# LEDS2.net
KiCad netlist of a schematic drawn in Altium Designer
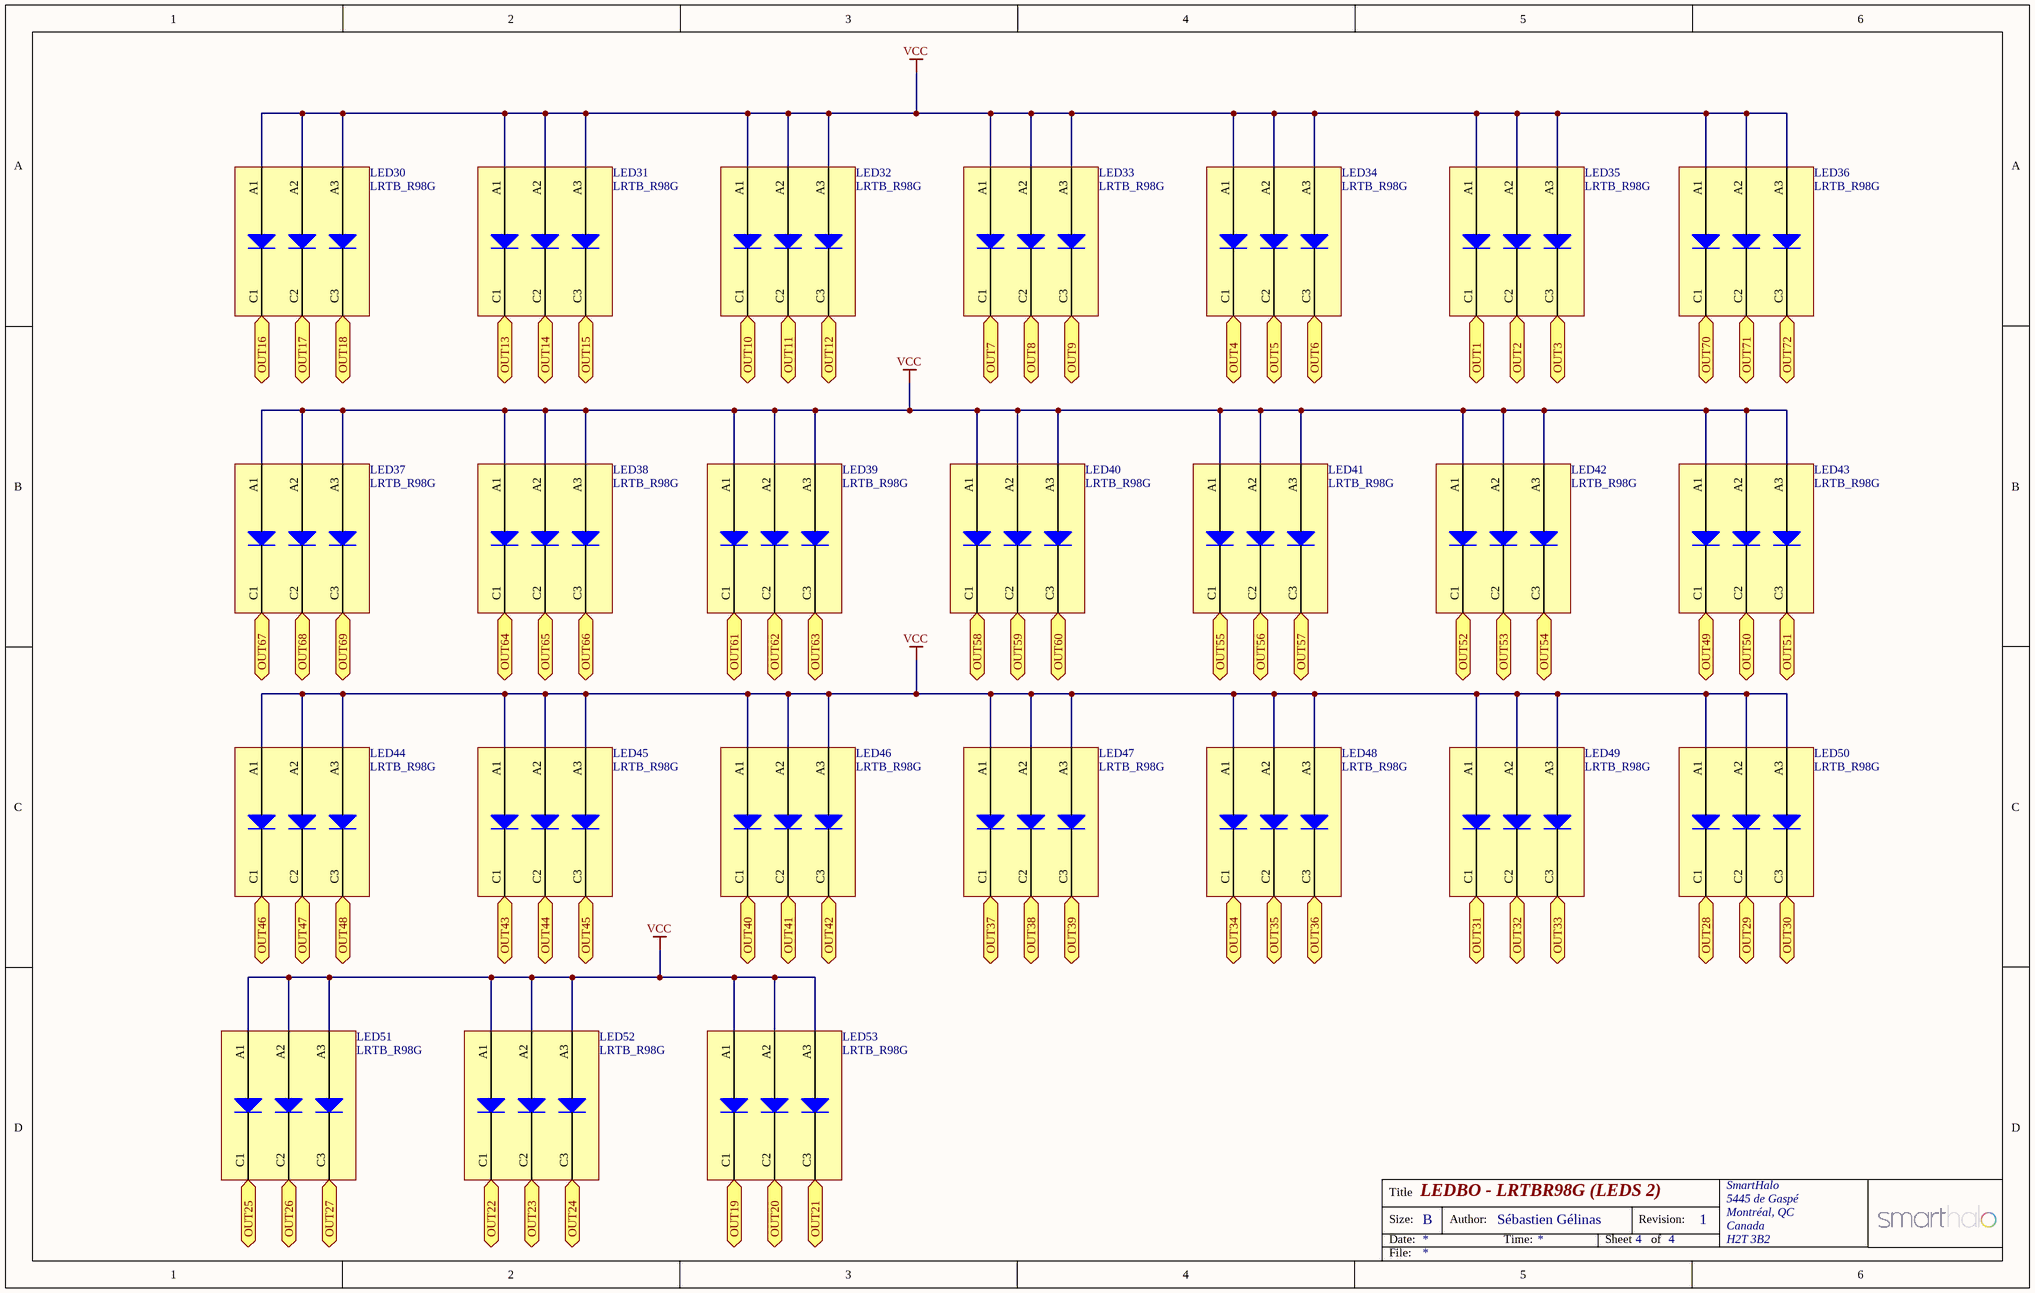
[diagram p0: LEDS2.SchDoc]

(export (version "E")
  (design (tool "Eeschema 10.0.6"))
  (components
    (comp (ref "LED30")
      (value "LRTB_R98G")
      (footprint "LRTB_R98G")
      (description "IC RGB LED OSRAM")
      (fields (field (name "MANUFACTURER") "OSRAM"))
      (libsource (lib "SmartHalo_Symbols") (part "LRTB_R98G"))
    )
    (comp (ref "LED31")
      (value "LRTB_R98G")
      (footprint "LRTB_R98G")
      (description "IC RGB LED OSRAM")
      (fields (field (name "MANUFACTURER") "OSRAM"))
      (libsource (lib "SmartHalo_Symbols") (part "LRTB_R98G"))
    )
    (comp (ref "LED32")
      (value "LRTB_R98G")
      (footprint "LRTB_R98G")
      (description "IC RGB LED OSRAM")
      (fields (field (name "MANUFACTURER") "OSRAM"))
      (libsource (lib "SmartHalo_Symbols") (part "LRTB_R98G"))
    )
    (comp (ref "LED33")
      (value "LRTB_R98G")
      (footprint "LRTB_R98G")
      (description "IC RGB LED OSRAM")
      (fields (field (name "MANUFACTURER") "OSRAM"))
      (libsource (lib "SmartHalo_Symbols") (part "LRTB_R98G"))
    )
    (comp (ref "LED34")
      (value "LRTB_R98G")
      (footprint "LRTB_R98G")
      (description "IC RGB LED OSRAM")
      (fields (field (name "MANUFACTURER") "OSRAM"))
      (libsource (lib "SmartHalo_Symbols") (part "LRTB_R98G"))
    )
    (comp (ref "LED35")
      (value "LRTB_R98G")
      (footprint "LRTB_R98G")
      (description "IC RGB LED OSRAM")
      (fields (field (name "MANUFACTURER") "OSRAM"))
      (libsource (lib "SmartHalo_Symbols") (part "LRTB_R98G"))
    )
    (comp (ref "LED36")
      (value "LRTB_R98G")
      (footprint "LRTB_R98G")
      (description "IC RGB LED OSRAM")
      (fields (field (name "MANUFACTURER") "OSRAM"))
      (libsource (lib "SmartHalo_Symbols") (part "LRTB_R98G"))
    )
    (comp (ref "LED37")
      (value "LRTB_R98G")
      (footprint "LRTB_R98G")
      (description "IC RGB LED OSRAM")
      (fields (field (name "MANUFACTURER") "OSRAM"))
      (libsource (lib "SmartHalo_Symbols") (part "LRTB_R98G"))
    )
    (comp (ref "LED38")
      (value "LRTB_R98G")
      (footprint "LRTB_R98G")
      (description "IC RGB LED OSRAM")
      (fields (field (name "MANUFACTURER") "OSRAM"))
      (libsource (lib "SmartHalo_Symbols") (part "LRTB_R98G"))
    )
    (comp (ref "LED39")
      (value "LRTB_R98G")
      (footprint "LRTB_R98G")
      (description "IC RGB LED OSRAM")
      (fields (field (name "MANUFACTURER") "OSRAM"))
      (libsource (lib "SmartHalo_Symbols") (part "LRTB_R98G"))
    )
    (comp (ref "LED40")
      (value "LRTB_R98G")
      (footprint "LRTB_R98G")
      (description "IC RGB LED OSRAM")
      (fields (field (name "MANUFACTURER") "OSRAM"))
      (libsource (lib "SmartHalo_Symbols") (part "LRTB_R98G"))
    )
    (comp (ref "LED41")
      (value "LRTB_R98G")
      (footprint "LRTB_R98G")
      (description "IC RGB LED OSRAM")
      (fields (field (name "MANUFACTURER") "OSRAM"))
      (libsource (lib "SmartHalo_Symbols") (part "LRTB_R98G"))
    )
    (comp (ref "LED42")
      (value "LRTB_R98G")
      (footprint "LRTB_R98G")
      (description "IC RGB LED OSRAM")
      (fields (field (name "MANUFACTURER") "OSRAM"))
      (libsource (lib "SmartHalo_Symbols") (part "LRTB_R98G"))
    )
    (comp (ref "LED43")
      (value "LRTB_R98G")
      (footprint "LRTB_R98G")
      (description "IC RGB LED OSRAM")
      (fields (field (name "MANUFACTURER") "OSRAM"))
      (libsource (lib "SmartHalo_Symbols") (part "LRTB_R98G"))
    )
    (comp (ref "LED44")
      (value "LRTB_R98G")
      (footprint "LRTB_R98G")
      (description "IC RGB LED OSRAM")
      (fields (field (name "MANUFACTURER") "OSRAM"))
      (libsource (lib "SmartHalo_Symbols") (part "LRTB_R98G"))
    )
    (comp (ref "LED45")
      (value "LRTB_R98G")
      (footprint "LRTB_R98G")
      (description "IC RGB LED OSRAM")
      (fields (field (name "MANUFACTURER") "OSRAM"))
      (libsource (lib "SmartHalo_Symbols") (part "LRTB_R98G"))
    )
    (comp (ref "LED46")
      (value "LRTB_R98G")
      (footprint "LRTB_R98G")
      (description "IC RGB LED OSRAM")
      (fields (field (name "MANUFACTURER") "OSRAM"))
      (libsource (lib "SmartHalo_Symbols") (part "LRTB_R98G"))
    )
    (comp (ref "LED47")
      (value "LRTB_R98G")
      (footprint "LRTB_R98G")
      (description "IC RGB LED OSRAM")
      (fields (field (name "MANUFACTURER") "OSRAM"))
      (libsource (lib "SmartHalo_Symbols") (part "LRTB_R98G"))
    )
    (comp (ref "LED48")
      (value "LRTB_R98G")
      (footprint "LRTB_R98G")
      (description "IC RGB LED OSRAM")
      (fields (field (name "MANUFACTURER") "OSRAM"))
      (libsource (lib "SmartHalo_Symbols") (part "LRTB_R98G"))
    )
    (comp (ref "LED49")
      (value "LRTB_R98G")
      (footprint "LRTB_R98G")
      (description "IC RGB LED OSRAM")
      (fields (field (name "MANUFACTURER") "OSRAM"))
      (libsource (lib "SmartHalo_Symbols") (part "LRTB_R98G"))
    )
    (comp (ref "LED50")
      (value "LRTB_R98G")
      (footprint "LRTB_R98G")
      (description "IC RGB LED OSRAM")
      (fields (field (name "MANUFACTURER") "OSRAM"))
      (libsource (lib "SmartHalo_Symbols") (part "LRTB_R98G"))
    )
    (comp (ref "LED51")
      (value "LRTB_R98G")
      (footprint "LRTB_R98G")
      (description "IC RGB LED OSRAM")
      (fields (field (name "MANUFACTURER") "OSRAM"))
      (libsource (lib "SmartHalo_Symbols") (part "LRTB_R98G"))
    )
    (comp (ref "LED52")
      (value "LRTB_R98G")
      (footprint "LRTB_R98G")
      (description "IC RGB LED OSRAM")
      (fields (field (name "MANUFACTURER") "OSRAM"))
      (libsource (lib "SmartHalo_Symbols") (part "LRTB_R98G"))
    )
    (comp (ref "LED53")
      (value "LRTB_R98G")
      (footprint "LRTB_R98G")
      (description "IC RGB LED OSRAM")
      (fields (field (name "MANUFACTURER") "OSRAM"))
      (libsource (lib "SmartHalo_Symbols") (part "LRTB_R98G"))
    )
  )
  (nets
    (net (code "1") (name "/OUT1") (class "Default")
      (node (ref "LED35") (pin "C1") (pinfunction "Cathode_Blue_C1") (pintype "passive"))
    )
    (net (code "2") (name "/OUT2") (class "Default")
      (node (ref "LED35") (pin "C2") (pinfunction "Cathode_Green_C2") (pintype "passive"))
    )
    (net (code "3") (name "/OUT3") (class "Default")
      (node (ref "LED35") (pin "C3") (pinfunction "Cathode_Red_C3") (pintype "passive"))
    )
    (net (code "4") (name "/OUT4") (class "Default")
      (node (ref "LED34") (pin "C1") (pinfunction "Cathode_Blue_C1") (pintype "passive"))
    )
    (net (code "5") (name "/OUT5") (class "Default")
      (node (ref "LED34") (pin "C2") (pinfunction "Cathode_Green_C2") (pintype "passive"))
    )
    (net (code "6") (name "/OUT6") (class "Default")
      (node (ref "LED34") (pin "C3") (pinfunction "Cathode_Red_C3") (pintype "passive"))
    )
    (net (code "7") (name "/OUT7") (class "Default")
      (node (ref "LED33") (pin "C1") (pinfunction "Cathode_Blue_C1") (pintype "passive"))
    )
    (net (code "8") (name "/OUT8") (class "Default")
      (node (ref "LED33") (pin "C2") (pinfunction "Cathode_Green_C2") (pintype "passive"))
    )
    (net (code "9") (name "/OUT9") (class "Default")
      (node (ref "LED33") (pin "C3") (pinfunction "Cathode_Red_C3") (pintype "passive"))
    )
    (net (code "10") (name "/OUT10") (class "Default")
      (node (ref "LED32") (pin "C1") (pinfunction "Cathode_Blue_C1") (pintype "passive"))
    )
    (net (code "11") (name "/OUT11") (class "Default")
      (node (ref "LED32") (pin "C2") (pinfunction "Cathode_Green_C2") (pintype "passive"))
    )
    (net (code "12") (name "/OUT12") (class "Default")
      (node (ref "LED32") (pin "C3") (pinfunction "Cathode_Red_C3") (pintype "passive"))
    )
    (net (code "13") (name "/OUT13") (class "Default")
      (node (ref "LED31") (pin "C1") (pinfunction "Cathode_Blue_C1") (pintype "passive"))
    )
    (net (code "14") (name "/OUT14") (class "Default")
      (node (ref "LED31") (pin "C2") (pinfunction "Cathode_Green_C2") (pintype "passive"))
    )
    (net (code "15") (name "/OUT15") (class "Default")
      (node (ref "LED31") (pin "C3") (pinfunction "Cathode_Red_C3") (pintype "passive"))
    )
    (net (code "16") (name "/OUT16") (class "Default")
      (node (ref "LED30") (pin "C1") (pinfunction "Cathode_Blue_C1") (pintype "passive"))
    )
    (net (code "17") (name "/OUT17") (class "Default")
      (node (ref "LED30") (pin "C2") (pinfunction "Cathode_Green_C2") (pintype "passive"))
    )
    (net (code "18") (name "/OUT18") (class "Default")
      (node (ref "LED30") (pin "C3") (pinfunction "Cathode_Red_C3") (pintype "passive"))
    )
    (net (code "19") (name "/OUT19") (class "Default")
      (node (ref "LED53") (pin "C1") (pinfunction "Cathode_Blue_C1") (pintype "passive"))
    )
    (net (code "20") (name "/OUT20") (class "Default")
      (node (ref "LED53") (pin "C2") (pinfunction "Cathode_Green_C2") (pintype "passive"))
    )
    (net (code "21") (name "/OUT21") (class "Default")
      (node (ref "LED53") (pin "C3") (pinfunction "Cathode_Red_C3") (pintype "passive"))
    )
    (net (code "22") (name "/OUT22") (class "Default")
      (node (ref "LED52") (pin "C1") (pinfunction "Cathode_Blue_C1") (pintype "passive"))
    )
    (net (code "23") (name "/OUT23") (class "Default")
      (node (ref "LED52") (pin "C2") (pinfunction "Cathode_Green_C2") (pintype "passive"))
    )
    (net (code "24") (name "/OUT24") (class "Default")
      (node (ref "LED52") (pin "C3") (pinfunction "Cathode_Red_C3") (pintype "passive"))
    )
    (net (code "25") (name "/OUT25") (class "Default")
      (node (ref "LED51") (pin "C1") (pinfunction "Cathode_Blue_C1") (pintype "passive"))
    )
    (net (code "26") (name "/OUT26") (class "Default")
      (node (ref "LED51") (pin "C2") (pinfunction "Cathode_Green_C2") (pintype "passive"))
    )
    (net (code "27") (name "/OUT27") (class "Default")
      (node (ref "LED51") (pin "C3") (pinfunction "Cathode_Red_C3") (pintype "passive"))
    )
    (net (code "28") (name "/OUT28") (class "Default")
      (node (ref "LED50") (pin "C1") (pinfunction "Cathode_Blue_C1") (pintype "passive"))
    )
    (net (code "29") (name "/OUT29") (class "Default")
      (node (ref "LED50") (pin "C2") (pinfunction "Cathode_Green_C2") (pintype "passive"))
    )
    (net (code "30") (name "/OUT30") (class "Default")
      (node (ref "LED50") (pin "C3") (pinfunction "Cathode_Red_C3") (pintype "passive"))
    )
    (net (code "31") (name "/OUT31") (class "Default")
      (node (ref "LED49") (pin "C1") (pinfunction "Cathode_Blue_C1") (pintype "passive"))
    )
    (net (code "32") (name "/OUT32") (class "Default")
      (node (ref "LED49") (pin "C2") (pinfunction "Cathode_Green_C2") (pintype "passive"))
    )
    (net (code "33") (name "/OUT33") (class "Default")
      (node (ref "LED49") (pin "C3") (pinfunction "Cathode_Red_C3") (pintype "passive"))
    )
    (net (code "34") (name "/OUT34") (class "Default")
      (node (ref "LED48") (pin "C1") (pinfunction "Cathode_Blue_C1") (pintype "passive"))
    )
    (net (code "35") (name "/OUT35") (class "Default")
      (node (ref "LED48") (pin "C2") (pinfunction "Cathode_Green_C2") (pintype "passive"))
    )
    (net (code "36") (name "/OUT36") (class "Default")
      (node (ref "LED48") (pin "C3") (pinfunction "Cathode_Red_C3") (pintype "passive"))
    )
    (net (code "37") (name "/OUT37") (class "Default")
      (node (ref "LED47") (pin "C1") (pinfunction "Cathode_Blue_C1") (pintype "passive"))
    )
    (net (code "38") (name "/OUT38") (class "Default")
      (node (ref "LED47") (pin "C2") (pinfunction "Cathode_Green_C2") (pintype "passive"))
    )
    (net (code "39") (name "/OUT39") (class "Default")
      (node (ref "LED47") (pin "C3") (pinfunction "Cathode_Red_C3") (pintype "passive"))
    )
    (net (code "40") (name "/OUT40") (class "Default")
      (node (ref "LED46") (pin "C1") (pinfunction "Cathode_Blue_C1") (pintype "passive"))
    )
    (net (code "41") (name "/OUT41") (class "Default")
      (node (ref "LED46") (pin "C2") (pinfunction "Cathode_Green_C2") (pintype "passive"))
    )
    (net (code "42") (name "/OUT42") (class "Default")
      (node (ref "LED46") (pin "C3") (pinfunction "Cathode_Red_C3") (pintype "passive"))
    )
    (net (code "43") (name "/OUT43") (class "Default")
      (node (ref "LED45") (pin "C1") (pinfunction "Cathode_Blue_C1") (pintype "passive"))
    )
    (net (code "44") (name "/OUT44") (class "Default")
      (node (ref "LED45") (pin "C2") (pinfunction "Cathode_Green_C2") (pintype "passive"))
    )
    (net (code "45") (name "/OUT45") (class "Default")
      (node (ref "LED45") (pin "C3") (pinfunction "Cathode_Red_C3") (pintype "passive"))
    )
    (net (code "46") (name "/OUT46") (class "Default")
      (node (ref "LED44") (pin "C1") (pinfunction "Cathode_Blue_C1") (pintype "passive"))
    )
    (net (code "47") (name "/OUT47") (class "Default")
      (node (ref "LED44") (pin "C2") (pinfunction "Cathode_Green_C2") (pintype "passive"))
    )
    (net (code "48") (name "/OUT48") (class "Default")
      (node (ref "LED44") (pin "C3") (pinfunction "Cathode_Red_C3") (pintype "passive"))
    )
    (net (code "49") (name "/OUT49") (class "Default")
      (node (ref "LED43") (pin "C1") (pinfunction "Cathode_Blue_C1") (pintype "passive"))
    )
    (net (code "50") (name "/OUT50") (class "Default")
      (node (ref "LED43") (pin "C2") (pinfunction "Cathode_Green_C2") (pintype "passive"))
    )
    (net (code "51") (name "/OUT51") (class "Default")
      (node (ref "LED43") (pin "C3") (pinfunction "Cathode_Red_C3") (pintype "passive"))
    )
    (net (code "52") (name "/OUT52") (class "Default")
      (node (ref "LED42") (pin "C1") (pinfunction "Cathode_Blue_C1") (pintype "passive"))
    )
    (net (code "53") (name "/OUT53") (class "Default")
      (node (ref "LED42") (pin "C2") (pinfunction "Cathode_Green_C2") (pintype "passive"))
    )
    (net (code "54") (name "/OUT54") (class "Default")
      (node (ref "LED42") (pin "C3") (pinfunction "Cathode_Red_C3") (pintype "passive"))
    )
    (net (code "55") (name "/OUT55") (class "Default")
      (node (ref "LED41") (pin "C1") (pinfunction "Cathode_Blue_C1") (pintype "passive"))
    )
    (net (code "56") (name "/OUT56") (class "Default")
      (node (ref "LED41") (pin "C2") (pinfunction "Cathode_Green_C2") (pintype "passive"))
    )
    (net (code "57") (name "/OUT57") (class "Default")
      (node (ref "LED41") (pin "C3") (pinfunction "Cathode_Red_C3") (pintype "passive"))
    )
    (net (code "58") (name "/OUT58") (class "Default")
      (node (ref "LED40") (pin "C1") (pinfunction "Cathode_Blue_C1") (pintype "passive"))
    )
    (net (code "59") (name "/OUT59") (class "Default")
      (node (ref "LED40") (pin "C2") (pinfunction "Cathode_Green_C2") (pintype "passive"))
    )
    (net (code "60") (name "/OUT60") (class "Default")
      (node (ref "LED40") (pin "C3") (pinfunction "Cathode_Red_C3") (pintype "passive"))
    )
    (net (code "61") (name "/OUT61") (class "Default")
      (node (ref "LED39") (pin "C1") (pinfunction "Cathode_Blue_C1") (pintype "passive"))
    )
    (net (code "62") (name "/OUT62") (class "Default")
      (node (ref "LED39") (pin "C2") (pinfunction "Cathode_Green_C2") (pintype "passive"))
    )
    (net (code "63") (name "/OUT63") (class "Default")
      (node (ref "LED39") (pin "C3") (pinfunction "Cathode_Red_C3") (pintype "passive"))
    )
    (net (code "64") (name "/OUT64") (class "Default")
      (node (ref "LED38") (pin "C1") (pinfunction "Cathode_Blue_C1") (pintype "passive"))
    )
    (net (code "65") (name "/OUT65") (class "Default")
      (node (ref "LED38") (pin "C2") (pinfunction "Cathode_Green_C2") (pintype "passive"))
    )
    (net (code "66") (name "/OUT66") (class "Default")
      (node (ref "LED38") (pin "C3") (pinfunction "Cathode_Red_C3") (pintype "passive"))
    )
    (net (code "67") (name "/OUT67") (class "Default")
      (node (ref "LED37") (pin "C1") (pinfunction "Cathode_Blue_C1") (pintype "passive"))
    )
    (net (code "68") (name "/OUT68") (class "Default")
      (node (ref "LED37") (pin "C2") (pinfunction "Cathode_Green_C2") (pintype "passive"))
    )
    (net (code "69") (name "/OUT69") (class "Default")
      (node (ref "LED37") (pin "C3") (pinfunction "Cathode_Red_C3") (pintype "passive"))
    )
    (net (code "70") (name "/OUT70") (class "Default")
      (node (ref "LED36") (pin "C1") (pinfunction "Cathode_Blue_C1") (pintype "passive"))
    )
    (net (code "71") (name "/OUT71") (class "Default")
      (node (ref "LED36") (pin "C2") (pinfunction "Cathode_Green_C2") (pintype "passive"))
    )
    (net (code "72") (name "/OUT72") (class "Default")
      (node (ref "LED36") (pin "C3") (pinfunction "Cathode_Red_C3") (pintype "passive"))
    )
    (net (code "73") (name "VCC") (class "Default")
      (node (ref "LED30") (pin "A1") (pinfunction "Anode_Blue_A1") (pintype "passive"))
      (node (ref "LED30") (pin "A2") (pinfunction "Anode_Green_A2") (pintype "passive"))
      (node (ref "LED30") (pin "A3") (pinfunction "Anode_Red_A3") (pintype "passive"))
      (node (ref "LED31") (pin "A1") (pinfunction "Anode_Blue_A1") (pintype "passive"))
      (node (ref "LED31") (pin "A2") (pinfunction "Anode_Green_A2") (pintype "passive"))
      (node (ref "LED31") (pin "A3") (pinfunction "Anode_Red_A3") (pintype "passive"))
      (node (ref "LED32") (pin "A1") (pinfunction "Anode_Blue_A1") (pintype "passive"))
      (node (ref "LED32") (pin "A2") (pinfunction "Anode_Green_A2") (pintype "passive"))
      (node (ref "LED32") (pin "A3") (pinfunction "Anode_Red_A3") (pintype "passive"))
      (node (ref "LED33") (pin "A1") (pinfunction "Anode_Blue_A1") (pintype "passive"))
      (node (ref "LED33") (pin "A2") (pinfunction "Anode_Green_A2") (pintype "passive"))
      (node (ref "LED33") (pin "A3") (pinfunction "Anode_Red_A3") (pintype "passive"))
      (node (ref "LED34") (pin "A1") (pinfunction "Anode_Blue_A1") (pintype "passive"))
      (node (ref "LED34") (pin "A2") (pinfunction "Anode_Green_A2") (pintype "passive"))
      (node (ref "LED34") (pin "A3") (pinfunction "Anode_Red_A3") (pintype "passive"))
      (node (ref "LED35") (pin "A1") (pinfunction "Anode_Blue_A1") (pintype "passive"))
      (node (ref "LED35") (pin "A2") (pinfunction "Anode_Green_A2") (pintype "passive"))
      (node (ref "LED35") (pin "A3") (pinfunction "Anode_Red_A3") (pintype "passive"))
      (node (ref "LED36") (pin "A1") (pinfunction "Anode_Blue_A1") (pintype "passive"))
      (node (ref "LED36") (pin "A2") (pinfunction "Anode_Green_A2") (pintype "passive"))
      (node (ref "LED36") (pin "A3") (pinfunction "Anode_Red_A3") (pintype "passive"))
      (node (ref "LED37") (pin "A1") (pinfunction "Anode_Blue_A1") (pintype "passive"))
      (node (ref "LED37") (pin "A2") (pinfunction "Anode_Green_A2") (pintype "passive"))
      (node (ref "LED37") (pin "A3") (pinfunction "Anode_Red_A3") (pintype "passive"))
      (node (ref "LED38") (pin "A1") (pinfunction "Anode_Blue_A1") (pintype "passive"))
      (node (ref "LED38") (pin "A2") (pinfunction "Anode_Green_A2") (pintype "passive"))
      (node (ref "LED38") (pin "A3") (pinfunction "Anode_Red_A3") (pintype "passive"))
      (node (ref "LED39") (pin "A1") (pinfunction "Anode_Blue_A1") (pintype "passive"))
      (node (ref "LED39") (pin "A2") (pinfunction "Anode_Green_A2") (pintype "passive"))
      (node (ref "LED39") (pin "A3") (pinfunction "Anode_Red_A3") (pintype "passive"))
      (node (ref "LED40") (pin "A1") (pinfunction "Anode_Blue_A1") (pintype "passive"))
      (node (ref "LED40") (pin "A2") (pinfunction "Anode_Green_A2") (pintype "passive"))
      (node (ref "LED40") (pin "A3") (pinfunction "Anode_Red_A3") (pintype "passive"))
      (node (ref "LED41") (pin "A1") (pinfunction "Anode_Blue_A1") (pintype "passive"))
      (node (ref "LED41") (pin "A2") (pinfunction "Anode_Green_A2") (pintype "passive"))
      (node (ref "LED41") (pin "A3") (pinfunction "Anode_Red_A3") (pintype "passive"))
      (node (ref "LED42") (pin "A1") (pinfunction "Anode_Blue_A1") (pintype "passive"))
      (node (ref "LED42") (pin "A2") (pinfunction "Anode_Green_A2") (pintype "passive"))
      (node (ref "LED42") (pin "A3") (pinfunction "Anode_Red_A3") (pintype "passive"))
      (node (ref "LED43") (pin "A1") (pinfunction "Anode_Blue_A1") (pintype "passive"))
      (node (ref "LED43") (pin "A2") (pinfunction "Anode_Green_A2") (pintype "passive"))
      (node (ref "LED43") (pin "A3") (pinfunction "Anode_Red_A3") (pintype "passive"))
      (node (ref "LED44") (pin "A1") (pinfunction "Anode_Blue_A1") (pintype "passive"))
      (node (ref "LED44") (pin "A2") (pinfunction "Anode_Green_A2") (pintype "passive"))
      (node (ref "LED44") (pin "A3") (pinfunction "Anode_Red_A3") (pintype "passive"))
      (node (ref "LED45") (pin "A1") (pinfunction "Anode_Blue_A1") (pintype "passive"))
      (node (ref "LED45") (pin "A2") (pinfunction "Anode_Green_A2") (pintype "passive"))
      (node (ref "LED45") (pin "A3") (pinfunction "Anode_Red_A3") (pintype "passive"))
      (node (ref "LED46") (pin "A1") (pinfunction "Anode_Blue_A1") (pintype "passive"))
      (node (ref "LED46") (pin "A2") (pinfunction "Anode_Green_A2") (pintype "passive"))
      (node (ref "LED46") (pin "A3") (pinfunction "Anode_Red_A3") (pintype "passive"))
      (node (ref "LED47") (pin "A1") (pinfunction "Anode_Blue_A1") (pintype "passive"))
      (node (ref "LED47") (pin "A2") (pinfunction "Anode_Green_A2") (pintype "passive"))
      (node (ref "LED47") (pin "A3") (pinfunction "Anode_Red_A3") (pintype "passive"))
      (node (ref "LED48") (pin "A1") (pinfunction "Anode_Blue_A1") (pintype "passive"))
      (node (ref "LED48") (pin "A2") (pinfunction "Anode_Green_A2") (pintype "passive"))
      (node (ref "LED48") (pin "A3") (pinfunction "Anode_Red_A3") (pintype "passive"))
      (node (ref "LED49") (pin "A1") (pinfunction "Anode_Blue_A1") (pintype "passive"))
      (node (ref "LED49") (pin "A2") (pinfunction "Anode_Green_A2") (pintype "passive"))
      (node (ref "LED49") (pin "A3") (pinfunction "Anode_Red_A3") (pintype "passive"))
      (node (ref "LED50") (pin "A1") (pinfunction "Anode_Blue_A1") (pintype "passive"))
      (node (ref "LED50") (pin "A2") (pinfunction "Anode_Green_A2") (pintype "passive"))
      (node (ref "LED50") (pin "A3") (pinfunction "Anode_Red_A3") (pintype "passive"))
      (node (ref "LED51") (pin "A1") (pinfunction "Anode_Blue_A1") (pintype "passive"))
      (node (ref "LED51") (pin "A2") (pinfunction "Anode_Green_A2") (pintype "passive"))
      (node (ref "LED51") (pin "A3") (pinfunction "Anode_Red_A3") (pintype "passive"))
      (node (ref "LED52") (pin "A1") (pinfunction "Anode_Blue_A1") (pintype "passive"))
      (node (ref "LED52") (pin "A2") (pinfunction "Anode_Green_A2") (pintype "passive"))
      (node (ref "LED52") (pin "A3") (pinfunction "Anode_Red_A3") (pintype "passive"))
      (node (ref "LED53") (pin "A1") (pinfunction "Anode_Blue_A1") (pintype "passive"))
      (node (ref "LED53") (pin "A2") (pinfunction "Anode_Green_A2") (pintype "passive"))
      (node (ref "LED53") (pin "A3") (pinfunction "Anode_Red_A3") (pintype "passive"))
    )
  )
)
